# main.net
KiCad netlist of a schematic drawn in EAGLE
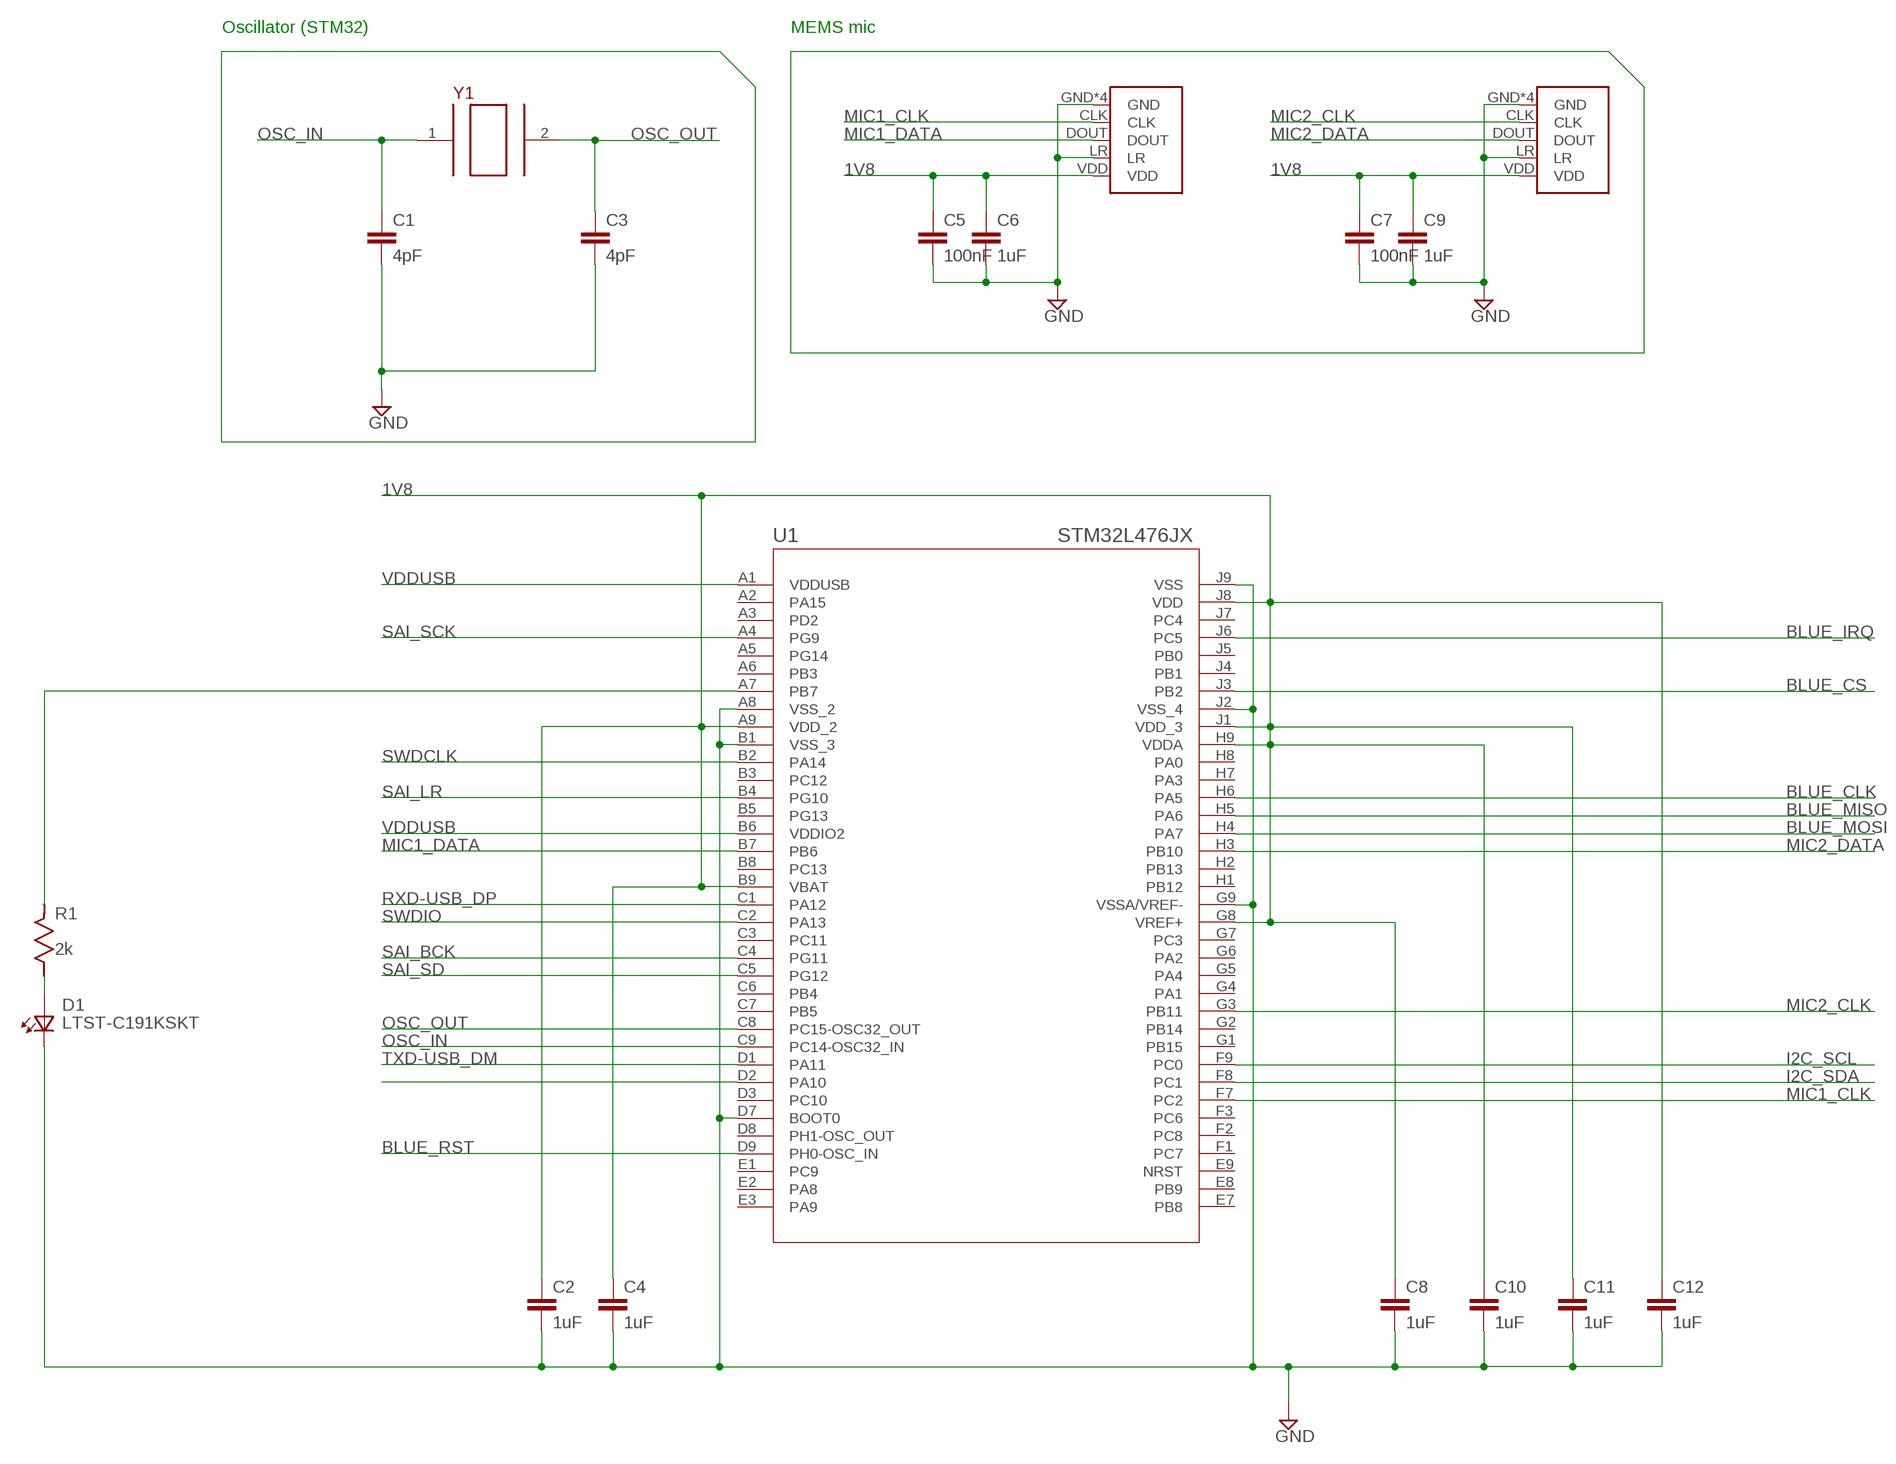
[diagram p0: schematic, sheet 1]
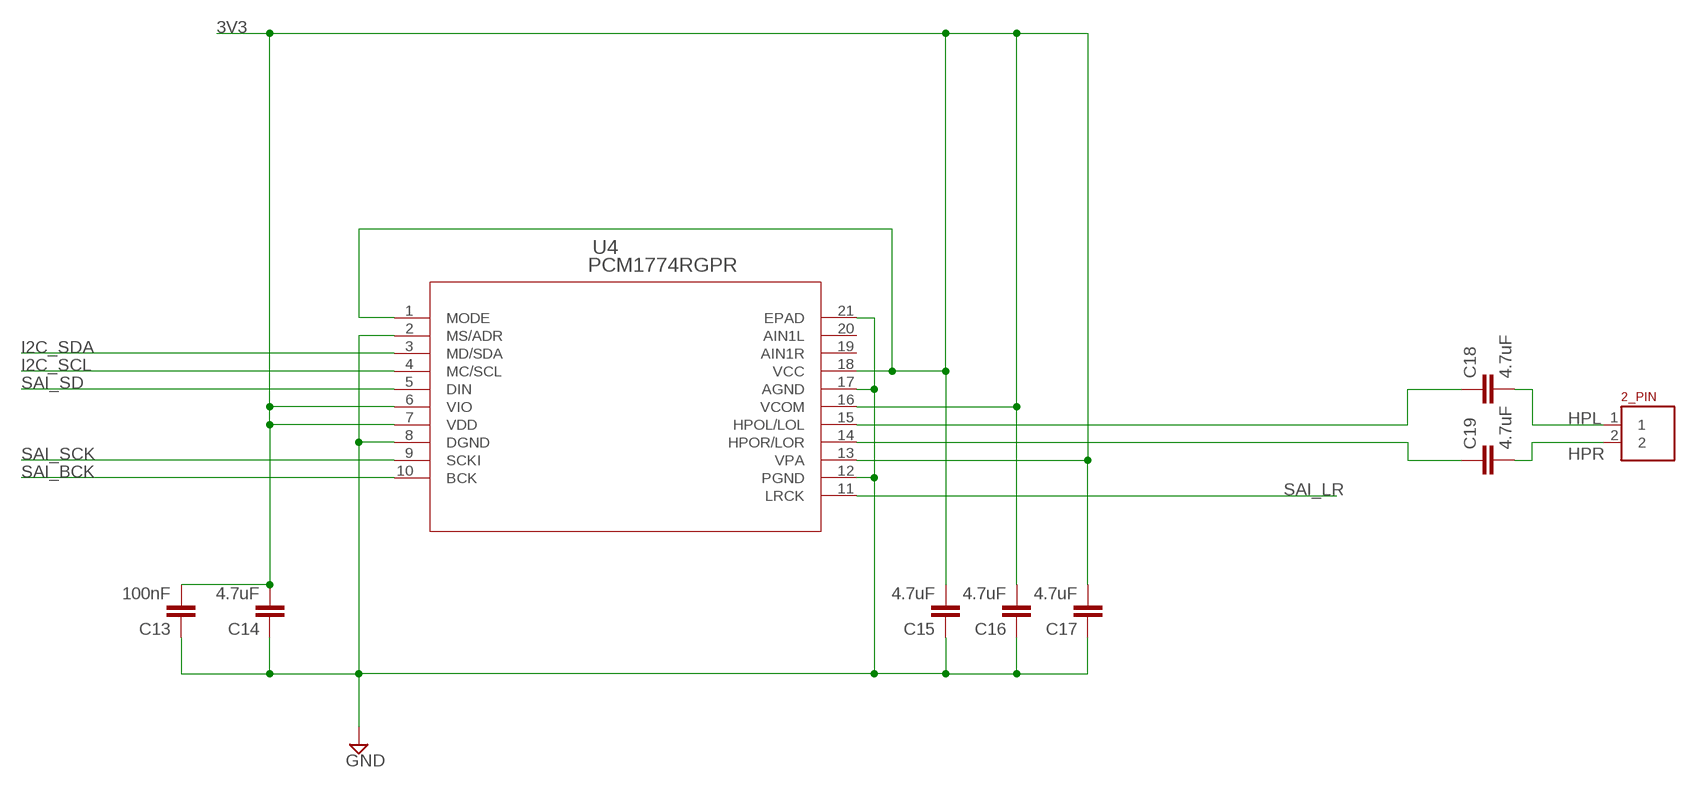
[diagram p1: schematic, sheet 2]
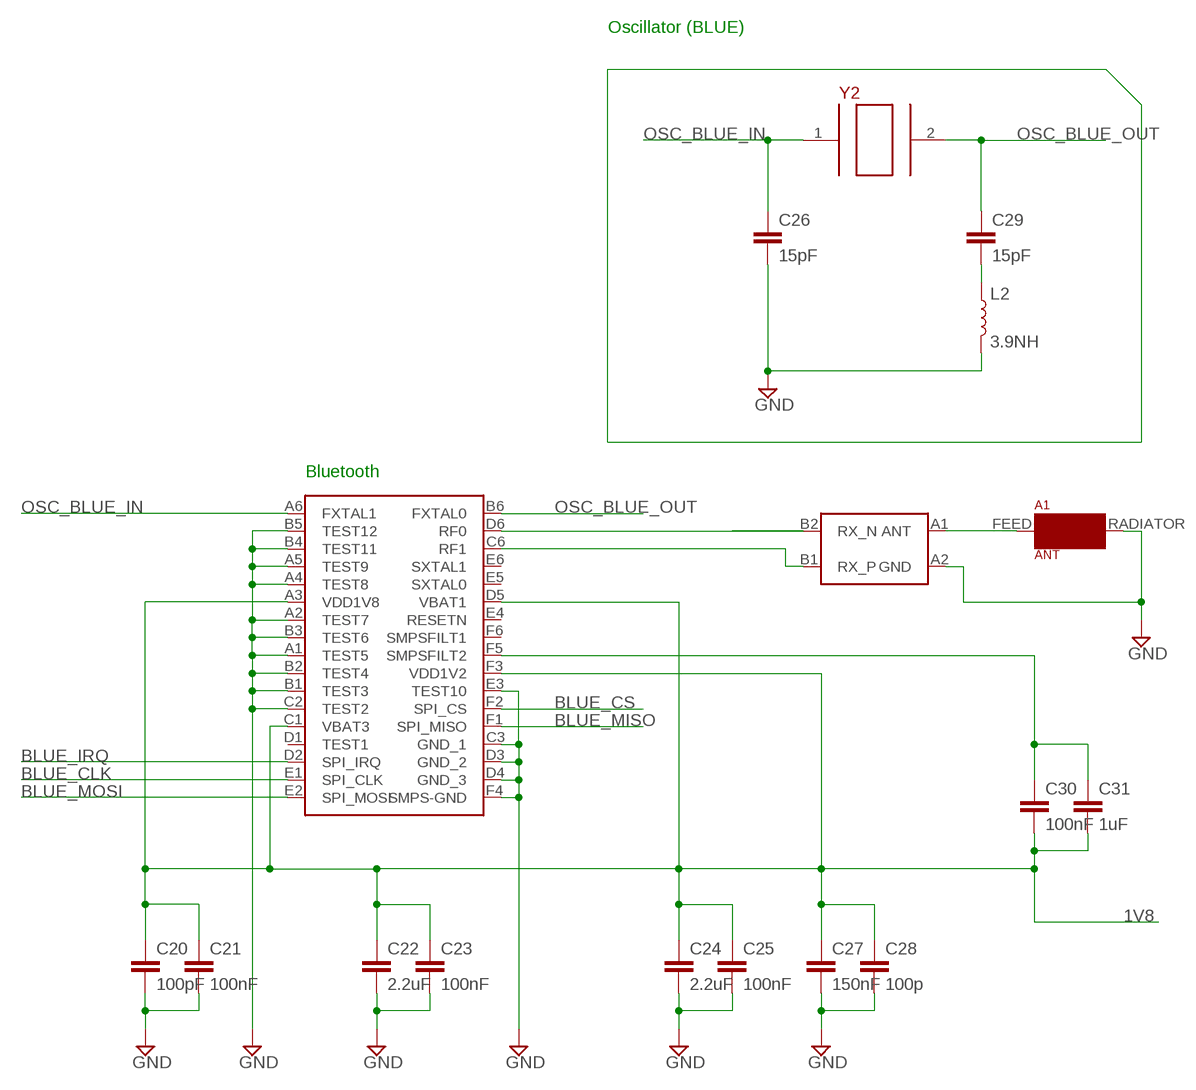
[diagram p2: schematic, sheet 3]
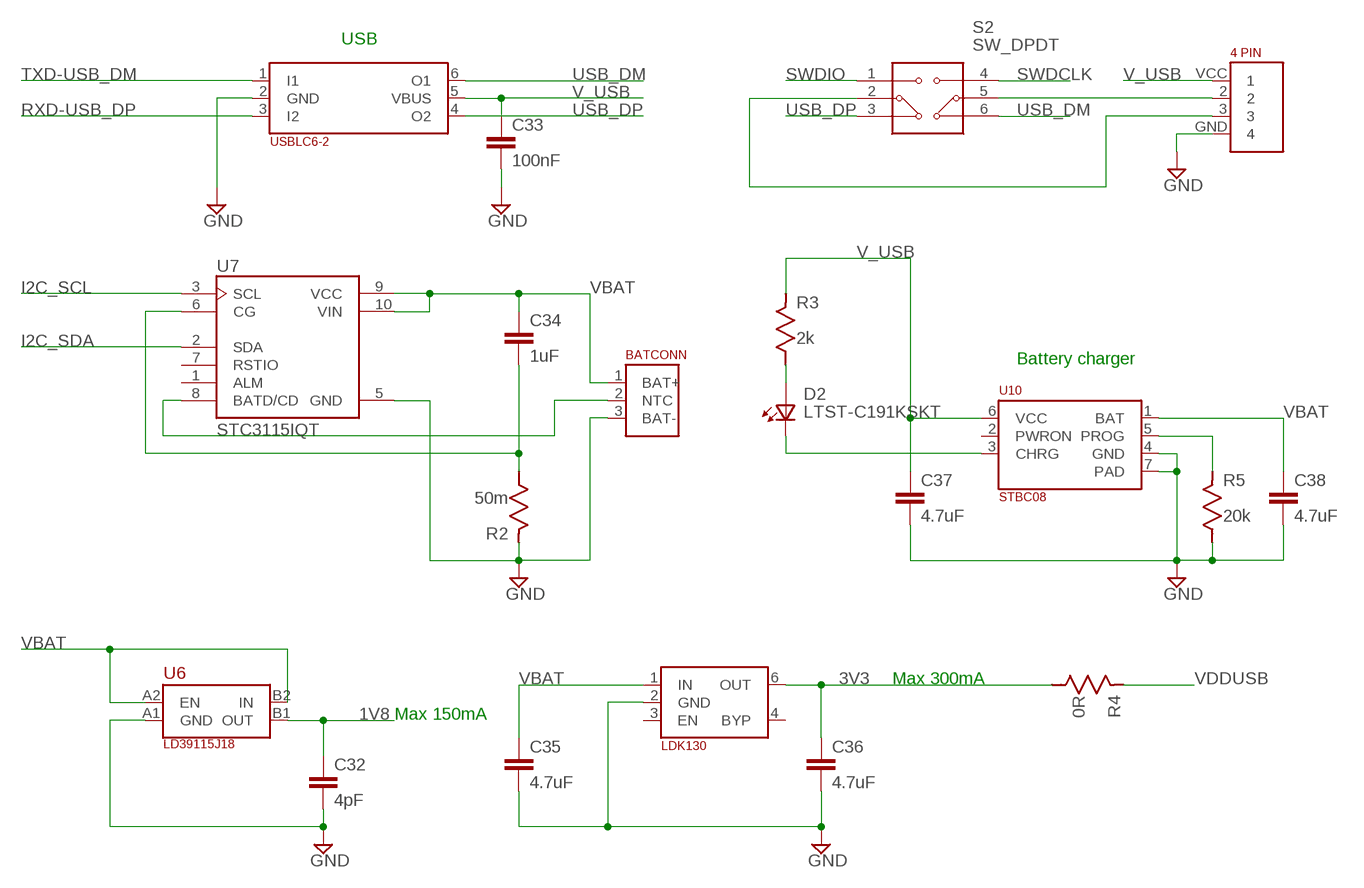
[diagram p3: schematic, sheet 4]

(export (version "E")
  (design (tool "Eeschema 10.0.6"))
  (components
    (comp (ref "A1")
      (value "ANT")
      (footprint "eagle-import:ANTPACK")
      (libsource (lib "eagle-import") (part "ANT"))
    )
    (comp (ref "C20")
      (value "100pF")
      (footprint "eagle-import:CAPC0603X30")
      (libsource (lib "eagle-import") (part "CAP0603"))
    )
    (comp (ref "C21")
      (value "100nF")
      (footprint "eagle-import:CAPC0603X30")
      (libsource (lib "eagle-import") (part "CAP0603"))
    )
    (comp (ref "C22")
      (value "2.2uF")
      (footprint "eagle-import:CAPC0603X30")
      (libsource (lib "eagle-import") (part "CAP0603"))
    )
    (comp (ref "C23")
      (value "100nF")
      (footprint "eagle-import:CAPC0603X30")
      (libsource (lib "eagle-import") (part "CAP0603"))
    )
    (comp (ref "C24")
      (value "2.2uF")
      (footprint "eagle-import:CAPC0603X30")
      (libsource (lib "eagle-import") (part "CAP0603"))
    )
    (comp (ref "C25")
      (value "100nF")
      (footprint "eagle-import:CAPC0603X30")
      (libsource (lib "eagle-import") (part "CAP0603"))
    )
    (comp (ref "C26")
      (value "15pF")
      (footprint "eagle-import:CAPC0603X30")
      (libsource (lib "eagle-import") (part "CAP0603"))
    )
    (comp (ref "C27")
      (value "150nF")
      (footprint "eagle-import:CAPC0603X30")
      (libsource (lib "eagle-import") (part "CAP0603"))
    )
    (comp (ref "C28")
      (value "100p")
      (footprint "eagle-import:CAPC0603X30")
      (libsource (lib "eagle-import") (part "CAP0603"))
    )
    (comp (ref "C29")
      (value "15pF")
      (footprint "eagle-import:CAPC0603X30")
      (libsource (lib "eagle-import") (part "CAP0603"))
    )
    (comp (ref "C30")
      (value "100nF")
      (footprint "eagle-import:CAPC0603X30")
      (libsource (lib "eagle-import") (part "CAP0603"))
    )
    (comp (ref "C31")
      (value "1uF")
      (footprint "eagle-import:CAPC0603X30")
      (libsource (lib "eagle-import") (part "CAP0603"))
    )
    (comp (ref "L1")
      (value "BALF-NRG-01D3")
      (footprint "eagle-import:FLIPCHIP")
      (libsource (lib "eagle-import") (part "BALF-NRG-01D3"))
    )
    (comp (ref "L2")
      (value "3.9NH")
      (footprint "eagle-import:0402")
      (libsource (lib "eagle-import") (part "INDUCTOR-0402-3.9NH"))
    )
    (comp (ref "U5")
      (value "BLUENRG-MS")
      (footprint "eagle-import:WLCSP34")
      (libsource (lib "eagle-import") (part "BLUENRG-MS"))
    )
    (comp (ref "Y2")
      (value "ABS06-107SMT")
      (footprint "eagle-import:CAPC2215X70")
      (libsource (lib "eagle-import") (part "ABS06-107SMT"))
    )
    (comp (ref "C1")
      (value "4pF")
      (footprint "eagle-import:CAPC0603X30")
      (libsource (lib "eagle-import") (part "CAP0603"))
    )
    (comp (ref "C2")
      (value "1uF")
      (footprint "eagle-import:CAPC0603X30")
      (libsource (lib "eagle-import") (part "CAP0603"))
    )
    (comp (ref "C3")
      (value "4pF")
      (footprint "eagle-import:CAPC0603X30")
      (libsource (lib "eagle-import") (part "CAP0603"))
    )
    (comp (ref "C4")
      (value "1uF")
      (footprint "eagle-import:CAPC0603X30")
      (libsource (lib "eagle-import") (part "CAP0603"))
    )
    (comp (ref "C5")
      (value "100nF")
      (footprint "eagle-import:CAPC0603X30")
      (libsource (lib "eagle-import") (part "CAP0603"))
    )
    (comp (ref "C6")
      (value "1uF")
      (footprint "eagle-import:CAPC0603X30")
      (libsource (lib "eagle-import") (part "CAP0603"))
    )
    (comp (ref "C7")
      (value "100nF")
      (footprint "eagle-import:CAPC0603X30")
      (libsource (lib "eagle-import") (part "CAP0603"))
    )
    (comp (ref "C8")
      (value "1uF")
      (footprint "eagle-import:CAPC0603X30")
      (libsource (lib "eagle-import") (part "CAP0603"))
    )
    (comp (ref "C9")
      (value "1uF")
      (footprint "eagle-import:CAPC0603X30")
      (libsource (lib "eagle-import") (part "CAP0603"))
    )
    (comp (ref "C10")
      (value "1uF")
      (footprint "eagle-import:CAPC0603X30")
      (libsource (lib "eagle-import") (part "CAP0603"))
    )
    (comp (ref "C11")
      (value "1uF")
      (footprint "eagle-import:CAPC0603X30")
      (libsource (lib "eagle-import") (part "CAP0603"))
    )
    (comp (ref "C12")
      (value "1uF")
      (footprint "eagle-import:CAPC0603X30")
      (libsource (lib "eagle-import") (part "CAP0603"))
    )
    (comp (ref "D1")
      (value "LTST-C191KSKT")
      (footprint "eagle-import:0603")
      (fields (field (name "MF") "Lite-On"))
      (libsource (lib "eagle-import") (part "LTST-C191KSKT"))
    )
    (comp (ref "R1")
      (value "2k")
      (footprint "eagle-import:CAPC0603X30")
      (libsource (lib "eagle-import") (part "RESISTOR"))
    )
    (comp (ref "U1")
      (value "STM32L476JX")
      (footprint "eagle-import:WLCSP72")
      (fields (field (name "MANUFACTURER_PART_NUMBER") "stm32l476jx"))
      (libsource (lib "eagle-import") (part "STM32L476JX"))
    )
    (comp (ref "U2")
      (value "MP34DT05-A")
      (footprint "eagle-import:MIC-PACK")
      (libsource (lib "eagle-import") (part "MP34DT05-A"))
    )
    (comp (ref "U3")
      (value "MP34DT05-A")
      (footprint "eagle-import:MIC-PACK")
      (libsource (lib "eagle-import") (part "MP34DT05-A"))
    )
    (comp (ref "Y1")
      (value "ABS06-107SMT")
      (footprint "eagle-import:CAPC2215X70")
      (libsource (lib "eagle-import") (part "ABS06-107SMT"))
    )
    (comp (ref "C32")
      (value "4pF")
      (footprint "eagle-import:CAPC0603X30")
      (libsource (lib "eagle-import") (part "CAP0603"))
    )
    (comp (ref "C33")
      (value "100nF")
      (footprint "eagle-import:CAPC0603X30")
      (libsource (lib "eagle-import") (part "CAP0603"))
    )
    (comp (ref "C34")
      (value "1uF")
      (footprint "eagle-import:CAPC0603X30")
      (libsource (lib "eagle-import") (part "CAP0603"))
    )
    (comp (ref "C35")
      (value "4.7uF")
      (footprint "eagle-import:CAPC0603X30")
      (libsource (lib "eagle-import") (part "CAP0603"))
    )
    (comp (ref "C36")
      (value "4.7uF")
      (footprint "eagle-import:CAPC0603X30")
      (libsource (lib "eagle-import") (part "CAP0603"))
    )
    (comp (ref "C37")
      (value "4.7uF")
      (footprint "eagle-import:CAPC0603X30")
      (libsource (lib "eagle-import") (part "CAP0603"))
    )
    (comp (ref "C38")
      (value "4.7uF")
      (footprint "eagle-import:CAPC0603X30")
      (libsource (lib "eagle-import") (part "CAP0603"))
    )
    (comp (ref "D2")
      (value "LTST-C191KSKT")
      (footprint "eagle-import:0603")
      (fields (field (name "MF") "Lite-On"))
      (libsource (lib "eagle-import") (part "LTST-C191KSKT"))
    )
    (comp (ref "J2")
      (value "BATT")
      (footprint "eagle-import:BATCONN")
      (libsource (lib "eagle-import") (part "BATT"))
    )
    (comp (ref "J3")
      (value "CS44")
      (footprint "eagle-import:CS44")
      (libsource (lib "eagle-import") (part "CS44"))
    )
    (comp (ref "R2")
      (value "50m")
      (footprint "eagle-import:CAPC0603X30")
      (libsource (lib "eagle-import") (part "RESISTOR"))
    )
    (comp (ref "R3")
      (value "2k")
      (footprint "eagle-import:CAPC0603X30")
      (libsource (lib "eagle-import") (part "RESISTOR"))
    )
    (comp (ref "R4")
      (value "0R")
      (footprint "eagle-import:CAPC0603X30")
      (libsource (lib "eagle-import") (part "RESISTOR"))
    )
    (comp (ref "R5")
      (value "20k")
      (footprint "eagle-import:CAPC0603X30")
      (libsource (lib "eagle-import") (part "RESISTOR"))
    )
    (comp (ref "S2")
      (value "SW_DPDT")
      (footprint "eagle-import:SW_DPDT")
      (libsource (lib "eagle-import") (part "SW_DPDT"))
    )
    (comp (ref "U6")
      (value "LD39115J18")
      (footprint "eagle-import:FLIPCHIP-2")
      (libsource (lib "eagle-import") (part "LD39115J18"))
    )
    (comp (ref "U7")
      (value "STC3115IQT")
      (footprint "eagle-import:SON50P300X200X60-10N")
      (fields (field (name "MF") "STMicroelectronics"))
      (libsource (lib "eagle-import") (part "STC3115IQT"))
    )
    (comp (ref "U8")
      (value "USBLC6-2")
      (footprint "eagle-import:SOT-666")
      (libsource (lib "eagle-import") (part "USBLC6-2"))
    )
    (comp (ref "U9")
      (value "LDK130")
      (footprint "eagle-import:DFN6")
      (libsource (lib "eagle-import") (part "LDK130"))
    )
    (comp (ref "U10")
      (value "STBC08")
      (footprint "eagle-import:DFN6")
      (libsource (lib "eagle-import") (part "STBC08"))
    )
    (comp (ref "C13")
      (value "100nF")
      (footprint "eagle-import:CAPC0603X30")
      (libsource (lib "eagle-import") (part "CAP0603"))
    )
    (comp (ref "C14")
      (value "4.7uF")
      (footprint "eagle-import:CAPC0603X30")
      (libsource (lib "eagle-import") (part "CAP0603"))
    )
    (comp (ref "C15")
      (value "4.7uF")
      (footprint "eagle-import:CAPC0603X30")
      (libsource (lib "eagle-import") (part "CAP0603"))
    )
    (comp (ref "C16")
      (value "4.7uF")
      (footprint "eagle-import:CAPC0603X30")
      (libsource (lib "eagle-import") (part "CAP0603"))
    )
    (comp (ref "C17")
      (value "4.7uF")
      (footprint "eagle-import:CAPC0603X30")
      (libsource (lib "eagle-import") (part "CAP0603"))
    )
    (comp (ref "C18")
      (value "4.7uF")
      (footprint "eagle-import:CAPC0603X30")
      (libsource (lib "eagle-import") (part "CAP0603"))
    )
    (comp (ref "C19")
      (value "4.7uF")
      (footprint "eagle-import:CAPC0603X30")
      (libsource (lib "eagle-import") (part "CAP0603"))
    )
    (comp (ref "J1")
      (value "2PIN")
      (footprint "eagle-import:2PINCON")
      (libsource (lib "eagle-import") (part "2PIN"))
    )
    (comp (ref "U4")
      (value "PCM1774RGPR")
      (footprint "eagle-import:RGP20_2P7X2P7")
      (libsource (lib "eagle-import") (part "PCM1774RGPR"))
    )
  )
  (nets
    (net (code "1") (name "1V8") (class "Default")
      (node (ref "C10") (pin "1") (pinfunction "1_1") (pintype "passive"))
      (node (ref "C11") (pin "1") (pinfunction "1_1") (pintype "passive"))
      (node (ref "C12") (pin "1") (pinfunction "1_1") (pintype "passive"))
      (node (ref "C2") (pin "1") (pinfunction "1_1") (pintype "passive"))
      (node (ref "C20") (pin "1") (pinfunction "1_1") (pintype "passive"))
      (node (ref "C21") (pin "1") (pinfunction "1_1") (pintype "passive"))
      (node (ref "C22") (pin "1") (pinfunction "1_1") (pintype "passive"))
      (node (ref "C23") (pin "1") (pinfunction "1_1") (pintype "passive"))
      (node (ref "C24") (pin "1") (pinfunction "1_1") (pintype "passive"))
      (node (ref "C25") (pin "1") (pinfunction "1_1") (pintype "passive"))
      (node (ref "C27") (pin "1") (pinfunction "1_1") (pintype "passive"))
      (node (ref "C28") (pin "1") (pinfunction "1_1") (pintype "passive"))
      (node (ref "C30") (pin "2") (pinfunction "2_2") (pintype "passive"))
      (node (ref "C31") (pin "2") (pinfunction "2_2") (pintype "passive"))
      (node (ref "C32") (pin "1") (pinfunction "1_1") (pintype "passive"))
      (node (ref "C4") (pin "1") (pinfunction "1_1") (pintype "passive"))
      (node (ref "C5") (pin "1") (pinfunction "1_1") (pintype "passive"))
      (node (ref "C6") (pin "1") (pinfunction "1_1") (pintype "passive"))
      (node (ref "C7") (pin "1") (pinfunction "1_1") (pintype "passive"))
      (node (ref "C8") (pin "1") (pinfunction "1_1") (pintype "passive"))
      (node (ref "C9") (pin "1") (pinfunction "1_1") (pintype "passive"))
      (node (ref "U1") (pin "A9") (pinfunction "VDD_2_A9") (pintype "power_in"))
      (node (ref "U1") (pin "B9") (pinfunction "VBAT_B9") (pintype "power_in"))
      (node (ref "U1") (pin "G8") (pinfunction "VREF+_G8") (pintype "power_in"))
      (node (ref "U1") (pin "H9") (pinfunction "VDDA_H9") (pintype "power_in"))
      (node (ref "U1") (pin "J1") (pinfunction "VDD_3_J1") (pintype "power_in"))
      (node (ref "U1") (pin "J8") (pinfunction "VDD_J8") (pintype "power_in"))
      (node (ref "U2") (pin "VDD") (pinfunction "VDD_VDD") (pintype "bidirectional"))
      (node (ref "U3") (pin "VDD") (pinfunction "VDD_VDD") (pintype "bidirectional"))
      (node (ref "U5") (pin "A3") (pinfunction "VDD1V8_A3") (pintype "power_in"))
      (node (ref "U5") (pin "C1") (pinfunction "VBAT3_C1") (pintype "power_in"))
      (node (ref "U5") (pin "D5") (pinfunction "VBAT1_D5") (pintype "power_in"))
      (node (ref "U5") (pin "F3") (pinfunction "VDD1V2_F3") (pintype "power_in"))
      (node (ref "U6") (pin "B1") (pinfunction "OUT_B1") (pintype "bidirectional"))
    )
    (net (code "2") (name "3V3") (class "Default")
      (node (ref "C13") (pin "2") (pinfunction "2_2") (pintype "passive"))
      (node (ref "C14") (pin "2") (pinfunction "2_2") (pintype "passive"))
      (node (ref "C15") (pin "2") (pinfunction "2_2") (pintype "passive"))
      (node (ref "C16") (pin "2") (pinfunction "2_2") (pintype "passive"))
      (node (ref "C17") (pin "2") (pinfunction "2_2") (pintype "passive"))
      (node (ref "C36") (pin "1") (pinfunction "1_1") (pintype "passive"))
      (node (ref "R4") (pin "2") (pinfunction "2_2") (pintype "passive"))
      (node (ref "U4") (pin "1") (pinfunction "MODE_1") (pintype "input"))
      (node (ref "U4") (pin "13") (pinfunction "VPA_13") (pintype "power_in"))
      (node (ref "U4") (pin "16") (pinfunction "VCOM_16") (pintype "power_in"))
      (node (ref "U4") (pin "18") (pinfunction "VCC_18") (pintype "power_in"))
      (node (ref "U4") (pin "6") (pinfunction "VIO_6") (pintype "bidirectional"))
      (node (ref "U4") (pin "7") (pinfunction "VDD_7") (pintype "power_in"))
      (node (ref "U9") (pin "6") (pinfunction "OUT_6") (pintype "bidirectional"))
    )
    (net (code "3") (name "BLUE_CLK") (class "Default")
      (node (ref "U1") (pin "H6") (pinfunction "PA5_H6") (pintype "bidirectional"))
      (node (ref "U5") (pin "E1") (pinfunction "SPI_CLK_E1") (pintype "power_in"))
    )
    (net (code "4") (name "BLUE_CS") (class "Default")
      (node (ref "U1") (pin "J3") (pinfunction "PB2_J3") (pintype "bidirectional"))
      (node (ref "U5") (pin "F2") (pinfunction "SPI_CS_F2") (pintype "power_in"))
    )
    (net (code "5") (name "BLUE_IRQ") (class "Default")
      (node (ref "U1") (pin "J6") (pinfunction "PC5_J6") (pintype "bidirectional"))
      (node (ref "U5") (pin "D2") (pinfunction "SPI_IRQ_D2") (pintype "power_in"))
    )
    (net (code "6") (name "BLUE_MISO") (class "Default")
      (node (ref "U1") (pin "H5") (pinfunction "PA6_H5") (pintype "bidirectional"))
      (node (ref "U5") (pin "F1") (pinfunction "SPI_MISO_F1") (pintype "power_in"))
    )
    (net (code "7") (name "BLUE_MOSI") (class "Default")
      (node (ref "U1") (pin "H4") (pinfunction "PA7_H4") (pintype "bidirectional"))
      (node (ref "U5") (pin "E2") (pinfunction "SPI_MOSI_E2") (pintype "power_in"))
    )
    (net (code "8") (name "BLUE_RST") (class "Default")
      (node (ref "U1") (pin "D9") (pinfunction "PH0-OSC_IN_D9") (pintype "bidirectional"))
    )
    (net (code "9") (name "GND") (class "Default")
      (node (ref "A1") (pin "RADIATOR") (pinfunction "P$2_RADIATOR") (pintype "bidirectional"))
      (node (ref "C1") (pin "2") (pinfunction "2_2") (pintype "passive"))
      (node (ref "C10") (pin "2") (pinfunction "2_2") (pintype "passive"))
      (node (ref "C11") (pin "2") (pinfunction "2_2") (pintype "passive"))
      (node (ref "C12") (pin "2") (pinfunction "2_2") (pintype "passive"))
      (node (ref "C13") (pin "1") (pinfunction "1_1") (pintype "passive"))
      (node (ref "C14") (pin "1") (pinfunction "1_1") (pintype "passive"))
      (node (ref "C15") (pin "1") (pinfunction "1_1") (pintype "passive"))
      (node (ref "C16") (pin "1") (pinfunction "1_1") (pintype "passive"))
      (node (ref "C17") (pin "1") (pinfunction "1_1") (pintype "passive"))
      (node (ref "C2") (pin "2") (pinfunction "2_2") (pintype "passive"))
      (node (ref "C20") (pin "2") (pinfunction "2_2") (pintype "passive"))
      (node (ref "C21") (pin "2") (pinfunction "2_2") (pintype "passive"))
      (node (ref "C22") (pin "2") (pinfunction "2_2") (pintype "passive"))
      (node (ref "C23") (pin "2") (pinfunction "2_2") (pintype "passive"))
      (node (ref "C24") (pin "2") (pinfunction "2_2") (pintype "passive"))
      (node (ref "C25") (pin "2") (pinfunction "2_2") (pintype "passive"))
      (node (ref "C26") (pin "2") (pinfunction "2_2") (pintype "passive"))
      (node (ref "C27") (pin "2") (pinfunction "2_2") (pintype "passive"))
      (node (ref "C28") (pin "2") (pinfunction "2_2") (pintype "passive"))
      (node (ref "C3") (pin "2") (pinfunction "2_2") (pintype "passive"))
      (node (ref "C32") (pin "2") (pinfunction "2_2") (pintype "passive"))
      (node (ref "C33") (pin "2") (pinfunction "2_2") (pintype "passive"))
      (node (ref "C35") (pin "2") (pinfunction "2_2") (pintype "passive"))
      (node (ref "C36") (pin "2") (pinfunction "2_2") (pintype "passive"))
      (node (ref "C37") (pin "2") (pinfunction "2_2") (pintype "passive"))
      (node (ref "C38") (pin "2") (pinfunction "2_2") (pintype "passive"))
      (node (ref "C4") (pin "2") (pinfunction "2_2") (pintype "passive"))
      (node (ref "C5") (pin "2") (pinfunction "2_2") (pintype "passive"))
      (node (ref "C6") (pin "2") (pinfunction "2_2") (pintype "passive"))
      (node (ref "C7") (pin "2") (pinfunction "2_2") (pintype "passive"))
      (node (ref "C8") (pin "2") (pinfunction "2_2") (pintype "passive"))
      (node (ref "C9") (pin "2") (pinfunction "2_2") (pintype "passive"))
      (node (ref "D1") (pin "1") (pinfunction "K2_1") (pintype "passive"))
      (node (ref "J2") (pin "3") (pinfunction "BAT-_3") (pintype "bidirectional"))
      (node (ref "J3") (pin "GND") (pinfunction "4_GND") (pintype "bidirectional"))
      (node (ref "L1") (pin "A2") (pinfunction "GND_A2") (pintype "power_in"))
      (node (ref "L2") (pin "2") (pinfunction "2_2") (pintype "passive"))
      (node (ref "R2") (pin "1") (pinfunction "1_1") (pintype "passive"))
      (node (ref "R5") (pin "2") (pinfunction "2_2") (pintype "passive"))
      (node (ref "U1") (pin "A8") (pinfunction "VSS_2_A8") (pintype "power_in"))
      (node (ref "U1") (pin "B1") (pinfunction "VSS_3_B1") (pintype "power_in"))
      (node (ref "U1") (pin "D7") (pinfunction "BOOT0_D7") (pintype "input"))
      (node (ref "U1") (pin "G9") (pinfunction "VSSA/VREF-_G9") (pintype "power_in"))
      (node (ref "U1") (pin "J2") (pinfunction "VSS_4_J2") (pintype "power_in"))
      (node (ref "U1") (pin "J9") (pinfunction "VSS_J9") (pintype "power_in"))
      (node (ref "U10") (pin "4") (pinfunction "GND_4") (pintype "bidirectional"))
      (node (ref "U10") (pin "7") (pinfunction "PAD_7") (pintype "bidirectional"))
      (node (ref "U2") (pin "GND") (pinfunction "GND_GND") (pintype "bidirectional"))
      (node (ref "U2") (pin "GND1") (pinfunction "GND_GND1") (pintype "bidirectional"))
      (node (ref "U2") (pin "GND2") (pinfunction "GND_GND2") (pintype "bidirectional"))
      (node (ref "U2") (pin "GND3") (pinfunction "GND_GND3") (pintype "bidirectional"))
      (node (ref "U2") (pin "LR") (pinfunction "LR_LR") (pintype "bidirectional"))
      (node (ref "U3") (pin "GND") (pinfunction "GND_GND") (pintype "bidirectional"))
      (node (ref "U3") (pin "GND1") (pinfunction "GND_GND1") (pintype "bidirectional"))
      (node (ref "U3") (pin "GND2") (pinfunction "GND_GND2") (pintype "bidirectional"))
      (node (ref "U3") (pin "GND3") (pinfunction "GND_GND3") (pintype "bidirectional"))
      (node (ref "U3") (pin "LR") (pinfunction "LR_LR") (pintype "bidirectional"))
      (node (ref "U4") (pin "12") (pinfunction "PGND_12") (pintype "power_in"))
      (node (ref "U4") (pin "17") (pinfunction "AGND_17") (pintype "power_in"))
      (node (ref "U4") (pin "2") (pinfunction "MS/ADR_2") (pintype "input"))
      (node (ref "U4") (pin "21") (pinfunction "EPAD_21") (pintype "passive"))
      (node (ref "U4") (pin "8") (pinfunction "DGND_8") (pintype "power_in"))
      (node (ref "U5") (pin "A1") (pinfunction "TEST5_A1") (pintype "power_in"))
      (node (ref "U5") (pin "A2") (pinfunction "TEST7_A2") (pintype "power_in"))
      (node (ref "U5") (pin "A4") (pinfunction "TEST8_A4") (pintype "power_in"))
      (node (ref "U5") (pin "A5") (pinfunction "TEST9_A5") (pintype "power_in"))
      (node (ref "U5") (pin "B1") (pinfunction "TEST3_B1") (pintype "power_in"))
      (node (ref "U5") (pin "B2") (pinfunction "TEST4_B2") (pintype "power_in"))
      (node (ref "U5") (pin "B3") (pinfunction "TEST6_B3") (pintype "power_in"))
      (node (ref "U5") (pin "B4") (pinfunction "TEST11_B4") (pintype "power_in"))
      (node (ref "U5") (pin "B5") (pinfunction "TEST12_B5") (pintype "power_in"))
      (node (ref "U5") (pin "C2") (pinfunction "TEST2_C2") (pintype "power_in"))
      (node (ref "U5") (pin "C3") (pinfunction "GND_1_C3") (pintype "power_in"))
      (node (ref "U5") (pin "D3") (pinfunction "GND_2_D3") (pintype "power_in"))
      (node (ref "U5") (pin "D4") (pinfunction "GND_3_D4") (pintype "power_in"))
      (node (ref "U5") (pin "E3") (pinfunction "TEST10_E3") (pintype "power_in"))
      (node (ref "U5") (pin "F4") (pinfunction "SMPS-GND_F4") (pintype "power_in"))
      (node (ref "U6") (pin "A1") (pinfunction "GND_A1") (pintype "bidirectional"))
      (node (ref "U7") (pin "5") (pinfunction "GND_5") (pintype "power_in"))
      (node (ref "U8") (pin "2") (pinfunction "GND_2") (pintype "bidirectional"))
      (node (ref "U9") (pin "2") (pinfunction "GND_2") (pintype "bidirectional"))
    )
    (net (code "10") (name "HPL") (class "Default")
      (node (ref "C18") (pin "2") (pinfunction "2_2") (pintype "passive"))
      (node (ref "J1") (pin "1") (pinfunction "1_1") (pintype "bidirectional"))
    )
    (net (code "11") (name "HPR") (class "Default")
      (node (ref "C19") (pin "2") (pinfunction "2_2") (pintype "passive"))
      (node (ref "J1") (pin "2") (pinfunction "2_2") (pintype "bidirectional"))
    )
    (net (code "12") (name "I2C_SCL") (class "Default")
      (node (ref "U1") (pin "F9") (pinfunction "PC0_F9") (pintype "bidirectional"))
      (node (ref "U4") (pin "4") (pinfunction "MC/SCL_4") (pintype "input"))
      (node (ref "U7") (pin "3") (pinfunction "SCL_3") (pintype "input"))
    )
    (net (code "13") (name "I2C_SDA") (class "Default")
      (node (ref "U1") (pin "F8") (pinfunction "PC1_F8") (pintype "bidirectional"))
      (node (ref "U4") (pin "3") (pinfunction "MD/SDA_3") (pintype "bidirectional"))
      (node (ref "U7") (pin "2") (pinfunction "SDA_2") (pintype "bidirectional"))
    )
    (net (code "14") (name "MIC1_CLK") (class "Default")
      (node (ref "U1") (pin "F7") (pinfunction "PC2_F7") (pintype "bidirectional"))
      (node (ref "U2") (pin "CLK") (pinfunction "CLK_CLK") (pintype "bidirectional"))
    )
    (net (code "15") (name "MIC1_DATA") (class "Default")
      (node (ref "U1") (pin "B7") (pinfunction "PB6_B7") (pintype "bidirectional"))
      (node (ref "U2") (pin "DOUT") (pinfunction "DOUT_DOUT") (pintype "bidirectional"))
    )
    (net (code "16") (name "MIC2_CLK") (class "Default")
      (node (ref "U1") (pin "G3") (pinfunction "PB11_G3") (pintype "bidirectional"))
      (node (ref "U3") (pin "CLK") (pinfunction "CLK_CLK") (pintype "bidirectional"))
    )
    (net (code "17") (name "MIC2_DATA") (class "Default")
      (node (ref "U1") (pin "H3") (pinfunction "PB10_H3") (pintype "bidirectional"))
      (node (ref "U3") (pin "DOUT") (pinfunction "DOUT_DOUT") (pintype "bidirectional"))
    )
    (net (code "18") (name "Net-(A1-P$1)") (class "Default")
      (node (ref "A1") (pin "FEED") (pinfunction "P$1_FEED") (pintype "bidirectional"))
      (node (ref "L1") (pin "A1") (pinfunction "ANT_A1") (pintype "power_in"))
    )
    (net (code "19") (name "Net-(C29-Pad2)") (class "Default")
      (node (ref "C29") (pin "2") (pinfunction "2_2") (pintype "passive"))
      (node (ref "L2") (pin "1") (pinfunction "1_1") (pintype "passive"))
    )
    (net (code "20") (name "Net-(D1-A2)") (class "Default")
      (node (ref "D1") (pin "2") (pinfunction "A2_2") (pintype "passive"))
      (node (ref "R1") (pin "2") (pinfunction "2_2") (pintype "passive"))
    )
    (net (code "21") (name "Net-(D2-A2)") (class "Default")
      (node (ref "D2") (pin "2") (pinfunction "A2_2") (pintype "passive"))
      (node (ref "R3") (pin "2") (pinfunction "2_2") (pintype "passive"))
    )
    (net (code "22") (name "Net-(D2-K2)") (class "Default")
      (node (ref "D2") (pin "1") (pinfunction "K2_1") (pintype "passive"))
      (node (ref "U10") (pin "3") (pinfunction "CHRG_3") (pintype "bidirectional"))
    )
    (net (code "23") (name "Net-(J2-NTC)") (class "Default")
      (node (ref "J2") (pin "2") (pinfunction "NTC_2") (pintype "bidirectional"))
      (node (ref "U7") (pin "8") (pinfunction "BATD/CD_8") (pintype "bidirectional"))
    )
    (net (code "24") (name "Net-(J3-Pad2)") (class "Default")
      (node (ref "J3") (pin "2") (pinfunction "2_2") (pintype "bidirectional"))
      (node (ref "S2") (pin "5") (pinfunction "5_5") (pintype "bidirectional"))
    )
    (net (code "25") (name "Net-(J3-Pad3)") (class "Default")
      (node (ref "J3") (pin "3") (pinfunction "3_3") (pintype "bidirectional"))
      (node (ref "S2") (pin "2") (pinfunction "2_2") (pintype "bidirectional"))
    )
    (net (code "26") (name "Net-(L1-RX_N)") (class "Default")
      (node (ref "L1") (pin "B2") (pinfunction "RX_N_B2") (pintype "power_in"))
      (node (ref "U5") (pin "D6") (pinfunction "RF0_D6") (pintype "power_in"))
    )
    (net (code "27") (name "Net-(L1-RX_P)") (class "Default")
      (node (ref "L1") (pin "B1") (pinfunction "RX_P_B1") (pintype "power_in"))
      (node (ref "U5") (pin "C6") (pinfunction "RF1_C6") (pintype "power_in"))
    )
    (net (code "28") (name "Net-(U1-PB7)") (class "Default")
      (node (ref "R1") (pin "1") (pinfunction "1_1") (pintype "passive"))
      (node (ref "U1") (pin "A7") (pinfunction "PB7_A7") (pintype "bidirectional"))
    )
    (net (code "29") (name "Net-(U4-HPOL{slash}LOL)") (class "Default")
      (node (ref "C18") (pin "1") (pinfunction "1_1") (pintype "passive"))
      (node (ref "U4") (pin "15") (pinfunction "HPOL/LOL_15") (pintype "output"))
    )
    (net (code "30") (name "Net-(U4-HPOR{slash}LOR)") (class "Default")
      (node (ref "C19") (pin "1") (pinfunction "1_1") (pintype "passive"))
      (node (ref "U4") (pin "14") (pinfunction "HPOR/LOR_14") (pintype "output"))
    )
    (net (code "31") (name "Net-(U5-SMPSFILT2)") (class "Default")
      (node (ref "C30") (pin "1") (pinfunction "1_1") (pintype "passive"))
      (node (ref "C31") (pin "1") (pinfunction "1_1") (pintype "passive"))
      (node (ref "U5") (pin "F5") (pinfunction "SMPSFILT2_F5") (pintype "power_in"))
    )
    (net (code "32") (name "Net-(U7-CG)") (class "Default")
      (node (ref "C34") (pin "2") (pinfunction "2_2") (pintype "passive"))
      (node (ref "R2") (pin "2") (pinfunction "2_2") (pintype "passive"))
      (node (ref "U7") (pin "6") (pinfunction "CG_6") (pintype "input"))
    )
    (net (code "33") (name "Net-(U10-PROG)") (class "Default")
      (node (ref "R5") (pin "1") (pinfunction "1_1") (pintype "passive"))
      (node (ref "U10") (pin "5") (pinfunction "PROG_5") (pintype "bidirectional"))
    )
    (net (code "34") (name "OSC_BLUE_IN") (class "Default")
      (node (ref "C26") (pin "1") (pinfunction "1_1") (pintype "passive"))
      (node (ref "U5") (pin "A6") (pinfunction "FXTAL1_A6") (pintype "power_in"))
      (node (ref "Y2") (pin "1") (pinfunction "P$1_1") (pintype "bidirectional"))
    )
    (net (code "35") (name "OSC_BLUE_OUT") (class "Default")
      (node (ref "C29") (pin "1") (pinfunction "1_1") (pintype "passive"))
      (node (ref "U5") (pin "B6") (pinfunction "FXTAL0_B6") (pintype "power_in"))
      (node (ref "Y2") (pin "2") (pinfunction "P$2_2") (pintype "bidirectional"))
    )
    (net (code "36") (name "OSC_IN") (class "Default")
      (node (ref "C1") (pin "1") (pinfunction "1_1") (pintype "passive"))
      (node (ref "U1") (pin "C9") (pinfunction "PC14-OSC32_IN_C9") (pintype "bidirectional"))
      (node (ref "Y1") (pin "1") (pinfunction "P$1_1") (pintype "bidirectional"))
    )
    (net (code "37") (name "OSC_OUT") (class "Default")
      (node (ref "C3") (pin "1") (pinfunction "1_1") (pintype "passive"))
      (node (ref "U1") (pin "C8") (pinfunction "PC15-OSC32_OUT_C8") (pintype "bidirectional"))
      (node (ref "Y1") (pin "2") (pinfunction "P$2_2") (pintype "bidirectional"))
    )
    (net (code "38") (name "RESETN") (class "Default")
      (node (ref "U5") (pin "E4") (pinfunction "RESETN_E4") (pintype "power_in"))
    )
    (net (code "39") (name "RXD-USB_DP") (class "Default")
      (node (ref "U1") (pin "C1") (pinfunction "PA12_C1") (pintype "bidirectional"))
      (node (ref "U8") (pin "3") (pinfunction "I2_3") (pintype "bidirectional"))
    )
    (net (code "40") (name "SAI_BCK") (class "Default")
      (node (ref "U1") (pin "C4") (pinfunction "PG11_C4") (pintype "bidirectional"))
      (node (ref "U4") (pin "10") (pinfunction "BCK_10") (pintype "bidirectional"))
    )
    (net (code "41") (name "SAI_LR") (class "Default")
      (node (ref "U1") (pin "B4") (pinfunction "PG10_B4") (pintype "bidirectional"))
      (node (ref "U4") (pin "11") (pinfunction "LRCK_11") (pintype "bidirectional"))
    )
    (net (code "42") (name "SAI_SCK") (class "Default")
      (node (ref "U1") (pin "A4") (pinfunction "PG9_A4") (pintype "bidirectional"))
      (node (ref "U4") (pin "9") (pinfunction "SCKI_9") (pintype "input"))
    )
    (net (code "43") (name "SAI_SD") (class "Default")
      (node (ref "U1") (pin "C5") (pinfunction "PG12_C5") (pintype "bidirectional"))
      (node (ref "U4") (pin "5") (pinfunction "DIN_5") (pintype "input"))
    )
    (net (code "44") (name "SMPSFILT1") (class "Default")
      (node (ref "U5") (pin "F6") (pinfunction "SMPSFILT1_F6") (pintype "power_in"))
    )
    (net (code "45") (name "SWDCLK") (class "Default")
      (node (ref "S2") (pin "4") (pinfunction "4_4") (pintype "bidirectional"))
      (node (ref "U1") (pin "B2") (pinfunction "PA14_B2") (pintype "bidirectional"))
    )
    (net (code "46") (name "SWDIO") (class "Default")
      (node (ref "S2") (pin "1") (pinfunction "1_1") (pintype "bidirectional"))
      (node (ref "U1") (pin "C2") (pinfunction "PA13_C2") (pintype "bidirectional"))
    )
    (net (code "47") (name "SXTAL0") (class "Default")
      (node (ref "U5") (pin "E5") (pinfunction "SXTAL0_E5") (pintype "power_in"))
    )
    (net (code "48") (name "SXTAL1") (class "Default")
      (node (ref "U5") (pin "E6") (pinfunction "SXTAL1_E6") (pintype "power_in"))
    )
    (net (code "49") (name "TEST1") (class "Default")
      (node (ref "U5") (pin "D1") (pinfunction "TEST1_D1") (pintype "power_in"))
    )
    (net (code "50") (name "TXD-USB_DM") (class "Default")
      (node (ref "U1") (pin "D1") (pinfunction "PA11_D1") (pintype "bidirectional"))
      (node (ref "U8") (pin "1") (pinfunction "I1_1") (pintype "bidirectional"))
    )
    (net (code "51") (name "USB_DM") (class "Default")
      (node (ref "S2") (pin "6") (pinfunction "6_6") (pintype "bidirectional"))
      (node (ref "U8") (pin "6") (pinfunction "O1_6") (pintype "bidirectional"))
    )
    (net (code "52") (name "USB_DP") (class "Default")
      (node (ref "S2") (pin "3") (pinfunction "3_3") (pintype "bidirectional"))
      (node (ref "U8") (pin "4") (pinfunction "O2_4") (pintype "bidirectional"))
    )
    (net (code "53") (name "VBAT") (class "Default")
      (node (ref "C34") (pin "1") (pinfunction "1_1") (pintype "passive"))
      (node (ref "C35") (pin "1") (pinfunction "1_1") (pintype "passive"))
      (node (ref "C38") (pin "1") (pinfunction "1_1") (pintype "passive"))
      (node (ref "J2") (pin "1") (pinfunction "BAT+_1") (pintype "bidirectional"))
      (node (ref "U10") (pin "1") (pinfunction "BAT_1") (pintype "bidirectional"))
      (node (ref "U6") (pin "A2") (pinfunction "EN_A2") (pintype "bidirectional"))
      (node (ref "U6") (pin "B2") (pinfunction "IN_B2") (pintype "bidirectional"))
      (node (ref "U7") (pin "10") (pinfunction "VIN_10") (pintype "power_in"))
      (node (ref "U7") (pin "9") (pinfunction "VCC_9") (pintype "power_in"))
      (node (ref "U9") (pin "1") (pinfunction "IN_1") (pintype "bidirectional"))
    )
    (net (code "54") (name "VDDUSB") (class "Default")
      (node (ref "R4") (pin "1") (pinfunction "1_1") (pintype "passive"))
      (node (ref "U1") (pin "A1") (pinfunction "VDDUSB_A1") (pintype "power_in"))
      (node (ref "U1") (pin "B6") (pinfunction "VDDIO2_B6") (pintype "power_in"))
    )
    (net (code "55") (name "V_USB") (class "Default")
      (node (ref "C33") (pin "1") (pinfunction "1_1") (pintype "passive"))
      (node (ref "C37") (pin "1") (pinfunction "1_1") (pintype "passive"))
      (node (ref "J3") (pin "VCC") (pinfunction "1_VCC") (pintype "bidirectional"))
      (node (ref "R3") (pin "1") (pinfunction "1_1") (pintype "passive"))
      (node (ref "U10") (pin "6") (pinfunction "VCC_6") (pintype "bidirectional"))
      (node (ref "U8") (pin "5") (pinfunction "VBUS_5") (pintype "bidirectional"))
    )
    (net (code "56") (name "unconnected-(U1-NRST-PadE9)") (class "Default")
      (node (ref "U1") (pin "E9") (pinfunction "NRST_E9") (pintype "bidirectional"))
    )
    (net (code "57") (name "unconnected-(U1-PA0-PadH8)") (class "Default")
      (node (ref "U1") (pin "H8") (pinfunction "PA0_H8") (pintype "bidirectional"))
    )
    (net (code "58") (name "unconnected-(U1-PA1-PadG4)") (class "Default")
      (node (ref "U1") (pin "G4") (pinfunction "PA1_G4") (pintype "bidirectional"))
    )
    (net (code "59") (name "unconnected-(U1-PA2-PadG6)") (class "Default")
      (node (ref "U1") (pin "G6") (pinfunction "PA2_G6") (pintype "bidirectional"))
    )
    (net (code "60") (name "unconnected-(U1-PA3-PadH7)") (class "Default")
      (node (ref "U1") (pin "H7") (pinfunction "PA3_H7") (pintype "bidirectional"))
    )
    (net (code "61") (name "unconnected-(U1-PA4-PadG5)") (class "Default")
      (node (ref "U1") (pin "G5") (pinfunction "PA4_G5") (pintype "bidirectional"))
    )
    (net (code "62") (name "unconnected-(U1-PA8-PadE2)") (class "Default")
      (node (ref "U1") (pin "E2") (pinfunction "PA8_E2") (pintype "bidirectional"))
    )
    (net (code "63") (name "unconnected-(U1-PA9-PadE3)") (class "Default")
      (node (ref "U1") (pin "E3") (pinfunction "PA9_E3") (pintype "bidirectional"))
    )
    (net (code "64") (name "unconnected-(U1-PA10-PadD2)") (class "Default")
      (node (ref "U1") (pin "D2") (pinfunction "PA10_D2") (pintype "bidirectional"))
    )
    (net (code "65") (name "unconnected-(U1-PA15-PadA2)") (class "Default")
      (node (ref "U1") (pin "A2") (pinfunction "PA15_A2") (pintype "bidirectional"))
    )
    (net (code "66") (name "unconnected-(U1-PB0-PadJ5)") (class "Default")
      (node (ref "U1") (pin "J5") (pinfunction "PB0_J5") (pintype "bidirectional"))
    )
    (net (code "67") (name "unconnected-(U1-PB1-PadJ4)") (class "Default")
      (node (ref "U1") (pin "J4") (pinfunction "PB1_J4") (pintype "bidirectional"))
    )
    (net (code "68") (name "unconnected-(U1-PB3-PadA6)") (class "Default")
      (node (ref "U1") (pin "A6") (pinfunction "PB3_A6") (pintype "bidirectional"))
    )
    (net (code "69") (name "unconnected-(U1-PB4-PadC6)") (class "Default")
      (node (ref "U1") (pin "C6") (pinfunction "PB4_C6") (pintype "bidirectional"))
    )
    (net (code "70") (name "unconnected-(U1-PB5-PadC7)") (class "Default")
      (node (ref "U1") (pin "C7") (pinfunction "PB5_C7") (pintype "bidirectional"))
    )
    (net (code "71") (name "unconnected-(U1-PB8-PadE7)") (class "Default")
      (node (ref "U1") (pin "E7") (pinfunction "PB8_E7") (pintype "bidirectional"))
    )
    (net (code "72") (name "unconnected-(U1-PB9-PadE8)") (class "Default")
      (node (ref "U1") (pin "E8") (pinfunction "PB9_E8") (pintype "bidirectional"))
    )
    (net (code "73") (name "unconnected-(U1-PB12-PadH1)") (class "Default")
      (node (ref "U1") (pin "H1") (pinfunction "PB12_H1") (pintype "bidirectional"))
    )
    (net (code "74") (name "unconnected-(U1-PB13-PadH2)") (class "Default")
      (node (ref "U1") (pin "H2") (pinfunction "PB13_H2") (pintype "bidirectional"))
    )
    (net (code "75") (name "unconnected-(U1-PB14-PadG2)") (class "Default")
      (node (ref "U1") (pin "G2") (pinfunction "PB14_G2") (pintype "bidirectional"))
    )
    (net (code "76") (name "unconnected-(U1-PB15-PadG1)") (class "Default")
      (node (ref "U1") (pin "G1") (pinfunction "PB15_G1") (pintype "bidirectional"))
    )
    (net (code "77") (name "unconnected-(U1-PC3-PadG7)") (class "Default")
      (node (ref "U1") (pin "G7") (pinfunction "PC3_G7") (pintype "bidirectional"))
    )
    (net (code "78") (name "unconnected-(U1-PC4-PadJ7)") (class "Default")
      (node (ref "U1") (pin "J7") (pinfunction "PC4_J7") (pintype "bidirectional"))
    )
    (net (code "79") (name "unconnected-(U1-PC6-PadF3)") (class "Default")
      (node (ref "U1") (pin "F3") (pinfunction "PC6_F3") (pintype "bidirectional"))
    )
    (net (code "80") (name "unconnected-(U1-PC7-PadF1)") (class "Default")
      (node (ref "U1") (pin "F1") (pinfunction "PC7_F1") (pintype "bidirectional"))
    )
    (net (code "81") (name "unconnected-(U1-PC8-PadF2)") (class "Default")
      (node (ref "U1") (pin "F2") (pinfunction "PC8_F2") (pintype "bidirectional"))
    )
    (net (code "82") (name "unconnected-(U1-PC9-PadE1)") (class "Default")
      (node (ref "U1") (pin "E1") (pinfunction "PC9_E1") (pintype "bidirectional"))
    )
    (net (code "83") (name "unconnected-(U1-PC10-PadD3)") (class "Default")
      (node (ref "U1") (pin "D3") (pinfunction "PC10_D3") (pintype "bidirectional"))
    )
    (net (code "84") (name "unconnected-(U1-PC11-PadC3)") (class "Default")
      (node (ref "U1") (pin "C3") (pinfunction "PC11_C3") (pintype "bidirectional"))
    )
    (net (code "85") (name "unconnected-(U1-PC12-PadB3)") (class "Default")
      (node (ref "U1") (pin "B3") (pinfunction "PC12_B3") (pintype "bidirectional"))
    )
    (net (code "86") (name "unconnected-(U1-PC13-PadB8)") (class "Default")
      (node (ref "U1") (pin "B8") (pinfunction "PC13_B8") (pintype "bidirectional"))
    )
    (net (code "87") (name "unconnected-(U1-PD2-PadA3)") (class "Default")
      (node (ref "U1") (pin "A3") (pinfunction "PD2_A3") (pintype "bidirectional"))
    )
    (net (code "88") (name "unconnected-(U1-PG13-PadB5)") (class "Default")
      (node (ref "U1") (pin "B5") (pinfunction "PG13_B5") (pintype "bidirectional"))
    )
    (net (code "89") (name "unconnected-(U1-PG14-PadA5)") (class "Default")
      (node (ref "U1") (pin "A5") (pinfunction "PG14_A5") (pintype "bidirectional"))
    )
    (net (code "90") (name "unconnected-(U1-PH1-OSC_OUT-PadD8)") (class "Default")
      (node (ref "U1") (pin "D8") (pinfunction "PH1-OSC_OUT_D8") (pintype "bidirectional"))
    )
    (net (code "91") (name "unconnected-(U4-AIN1L-Pad20)") (class "Default")
      (node (ref "U4") (pin "20") (pinfunction "AIN1L_20") (pintype "input"))
    )
    (net (code "92") (name "unconnected-(U4-AIN1R-Pad19)") (class "Default")
      (node (ref "U4") (pin "19") (pinfunction "AIN1R_19") (pintype "input"))
    )
    (net (code "93") (name "unconnected-(U7-ALM-Pad1)") (class "Default")
      (node (ref "U7") (pin "1") (pinfunction "ALM_1") (pintype "bidirectional"))
    )
    (net (code "94") (name "unconnected-(U7-RSTIO-Pad7)") (class "Default")
      (node (ref "U7") (pin "7") (pinfunction "RSTIO_7") (pintype "bidirectional"))
    )
    (net (code "95") (name "unconnected-(U9-BYP-Pad4)") (class "Default")
      (node (ref "U9") (pin "4") (pinfunction "BYP_4") (pintype "bidirectional"))
    )
    (net (code "96") (name "unconnected-(U9-EN-Pad3)") (class "Default")
      (node (ref "U9") (pin "3") (pinfunction "EN_3") (pintype "bidirectional"))
    )
    (net (code "97") (name "unconnected-(U10-PWRON-Pad2)") (class "Default")
      (node (ref "U10") (pin "2") (pinfunction "PWRON_2") (pintype "bidirectional"))
    )
  )
)
